# lvc.net
KiCad netlist of a schematic drawn in EAGLE
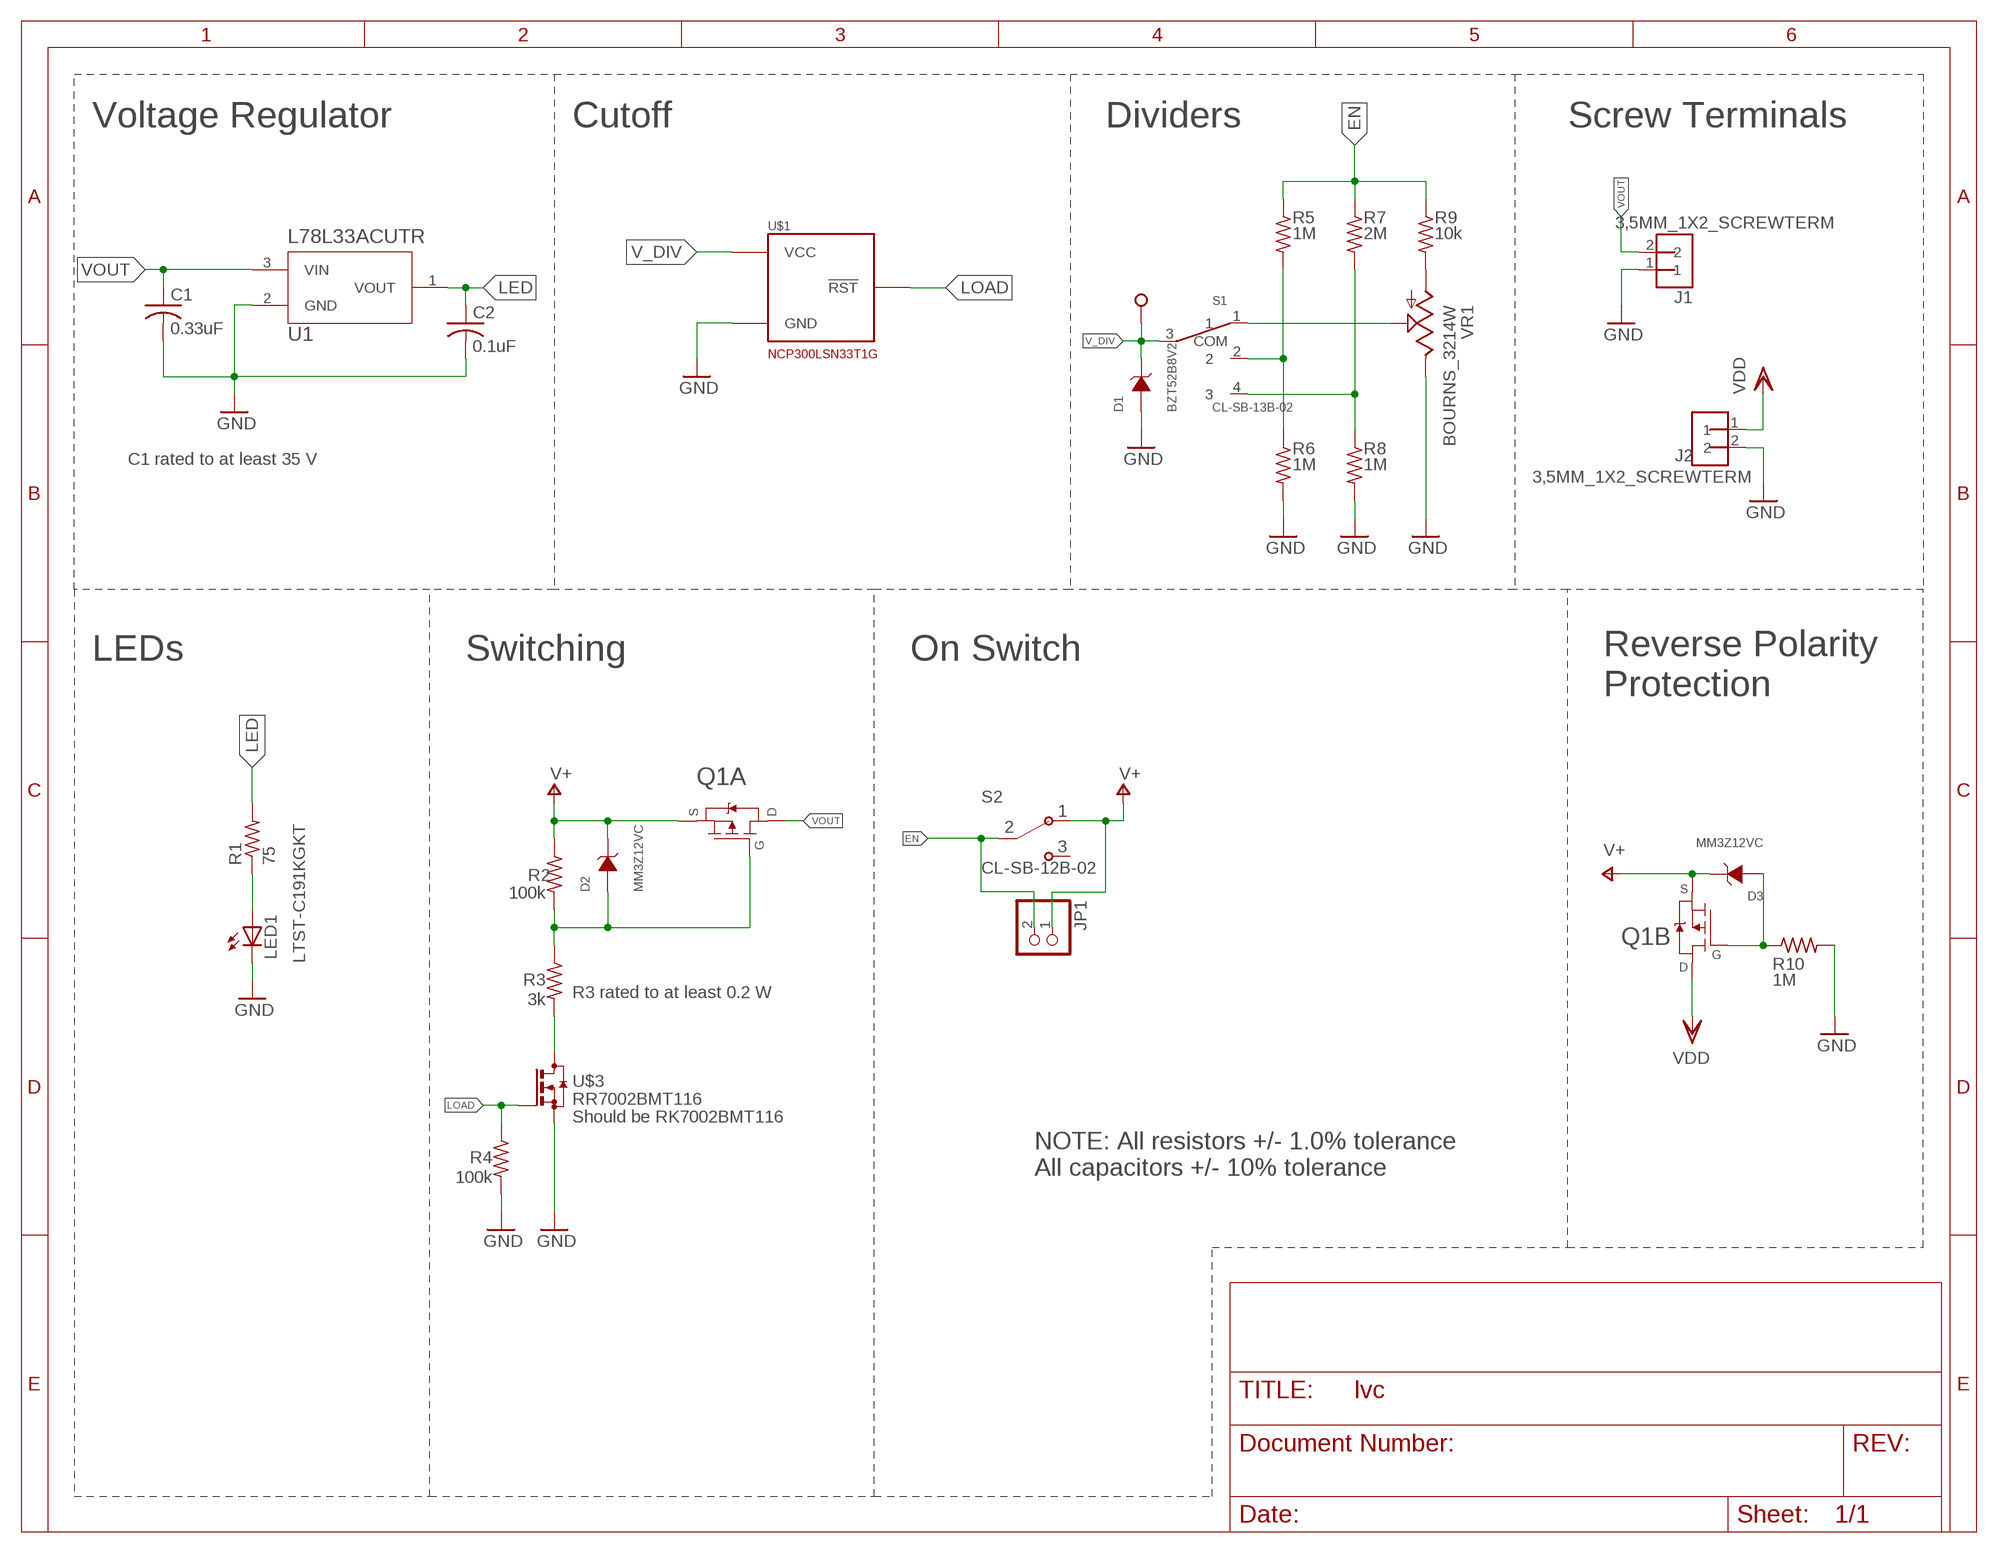
[diagram p0: schematic, sheet 1]

(export (version "E")
  (design (tool "Eeschema 10.0.6"))
  (components
    (comp (ref "C1")
      (value "0.33uF")
      (footprint "eagle-import:C0603")
      (libsource (lib "eagle-import") (part "C-USC0603"))
    )
    (comp (ref "C2")
      (value "0.1uF")
      (footprint "eagle-import:C0603")
      (libsource (lib "eagle-import") (part "C-USC0603"))
    )
    (comp (ref "D1")
      (value "BZT52B8V2")
      (footprint "eagle-import:SOD123")
      (libsource (lib "eagle-import") (part "BZT52B8V2"))
    )
    (comp (ref "D2")
      (value "MM3Z12VC")
      (footprint "eagle-import:SOD-323F")
      (libsource (lib "eagle-import") (part "MM3Z12VC"))
    )
    (comp (ref "D3")
      (value "MM3Z12VC")
      (footprint "eagle-import:SOD-323F")
      (libsource (lib "eagle-import") (part "MM3Z12VC"))
    )
    (comp (ref "J1")
      (value "3,5MM_1X2_SCREWTERM")
      (footprint "eagle-import:3.5MM_1X2")
      (libsource (lib "eagle-import") (part "3,5MM_1X2_SCREWTERM"))
    )
    (comp (ref "J2")
      (value "3,5MM_1X2_SCREWTERM")
      (footprint "eagle-import:3.5MM_1X2")
      (libsource (lib "eagle-import") (part "3,5MM_1X2_SCREWTERM"))
    )
    (comp (ref "JP1")
      (value "PINHD-1X2")
      (footprint "eagle-import:1X02")
      (libsource (lib "eagle-import") (part "PINHD-1X2"))
    )
    (comp (ref "LED1")
      (value "LEDCHIPLED_0603")
      (footprint "eagle-import:CHIPLED_0603")
      (libsource (lib "eagle-import") (part "LEDCHIPLED_0603"))
    )
    (comp (ref "Q1")
      (value "SI7997DP")
      (footprint "eagle-import:POWERPAK-SO-8-DUAL")
      (libsource (lib "eagle-import") (part "SI7997DP"))
    )
    (comp (ref "R1")
      (value "75")
      (footprint "eagle-import:R0603")
      (libsource (lib "eagle-import") (part "R-US_R0603"))
    )
    (comp (ref "R2")
      (value "100k")
      (footprint "eagle-import:R0603")
      (libsource (lib "eagle-import") (part "resistor_348_R-US_R0603"))
    )
    (comp (ref "R3")
      (value "3k")
      (footprint "eagle-import:R0603")
      (libsource (lib "eagle-import") (part "resistor_348_R-US_R0603"))
    )
    (comp (ref "R4")
      (value "100k")
      (footprint "eagle-import:R0603")
      (libsource (lib "eagle-import") (part "resistor_348_R-US_R0603"))
    )
    (comp (ref "R5")
      (value "1M")
      (footprint "eagle-import:R0603")
      (libsource (lib "eagle-import") (part "resistor_348_R-US_R0603"))
    )
    (comp (ref "R6")
      (value "1M")
      (footprint "eagle-import:R0603")
      (libsource (lib "eagle-import") (part "resistor_348_R-US_R0603"))
    )
    (comp (ref "R7")
      (value "2M")
      (footprint "eagle-import:R0603")
      (libsource (lib "eagle-import") (part "resistor_348_R-US_R0603"))
    )
    (comp (ref "R8")
      (value "1M")
      (footprint "eagle-import:R0603")
      (libsource (lib "eagle-import") (part "resistor_348_R-US_R0603"))
    )
    (comp (ref "R9")
      (value "10k")
      (footprint "eagle-import:R0603")
      (libsource (lib "eagle-import") (part "resistor_348_R-US_R0603"))
    )
    (comp (ref "R10")
      (value "1M")
      (footprint "eagle-import:R0603")
      (libsource (lib "eagle-import") (part "resistor_348_R-US_R0603"))
    )
    (comp (ref "S1")
      (value "CL-SB-13B-02")
      (footprint "eagle-import:CL-SB-13B")
      (libsource (lib "eagle-import") (part "CL-SB-13B-02"))
    )
    (comp (ref "S2")
      (value "CL-SB-12B-02")
      (footprint "eagle-import:CL-SB-12B")
      (libsource (lib "eagle-import") (part "CL-SB-12B-02"))
    )
    (comp (ref "TP1")
      (value "TESTPOINT")
      (footprint "eagle-import:TP_2.5MM")
      (libsource (lib "eagle-import") (part "TESTPOINT"))
    )
    (comp (ref "U$1")
      (value "NCP300LSN33T1G")
      (footprint "eagle-import:SOT23-5")
      (libsource (lib "eagle-import") (part "NCP300LSN33T1G"))
    )
    (comp (ref "U$3")
      (value "RR7002BMT116")
      (footprint "eagle-import:SOT23")
      (libsource (lib "eagle-import") (part "RR7002BMT116"))
    )
    (comp (ref "U1")
      (value "L78L33ACUTR")
      (footprint "eagle-import:SOT-89")
      (libsource (lib "eagle-import") (part "L78L33ACUTR"))
    )
    (comp (ref "VR1")
      (value "BOURNS_3214W")
      (footprint "eagle-import:J-LEAD_TOP_ADJ")
      (libsource (lib "eagle-import") (part "BOURNS_3214W"))
    )
  )
  (nets
    (net (code "1") (name "EN") (class "Default")
      (node (ref "JP1") (pin "2") (pinfunction "2_2") (pintype "passive"))
      (node (ref "R5") (pin "1") (pinfunction "1_1") (pintype "passive"))
      (node (ref "R7") (pin "1") (pinfunction "1_1") (pintype "passive"))
      (node (ref "R9") (pin "1") (pinfunction "1_1") (pintype "passive"))
      (node (ref "S2") (pin "1") (pinfunction "P$1_1") (pintype "bidirectional"))
    )
    (net (code "2") (name "GND") (class "Default")
      (node (ref "C1") (pin "2") (pinfunction "2_2") (pintype "passive"))
      (node (ref "C2") (pin "2") (pinfunction "2_2") (pintype "passive"))
      (node (ref "D1") (pin "A") (pinfunction "A_A") (pintype "bidirectional"))
      (node (ref "J1") (pin "1") (pinfunction "1_1") (pintype "bidirectional"))
      (node (ref "J2") (pin "2") (pinfunction "2_2") (pintype "bidirectional"))
      (node (ref "LED1") (pin "C") (pinfunction "C_C") (pintype "passive"))
      (node (ref "R10") (pin "2") (pinfunction "2_2") (pintype "passive"))
      (node (ref "R4") (pin "2") (pinfunction "2_2") (pintype "passive"))
      (node (ref "R6") (pin "2") (pinfunction "2_2") (pintype "passive"))
      (node (ref "R8") (pin "2") (pinfunction "2_2") (pintype "passive"))
      (node (ref "U$1") (pin "3") (pinfunction "GND_3") (pintype "power_in"))
      (node (ref "U$3") (pin "2") (pinfunction "S_2") (pintype "passive"))
      (node (ref "U1") (pin "2") (pinfunction "GND_2") (pintype "passive"))
      (node (ref "VR1") (pin "3") (pinfunction "E_3") (pintype "passive"))
    )
    (net (code "3") (name "LED") (class "Default")
      (node (ref "C2") (pin "1") (pinfunction "1_1") (pintype "passive"))
      (node (ref "R1") (pin "2") (pinfunction "2_2") (pintype "passive"))
      (node (ref "U1") (pin "1") (pinfunction "VOUT_1") (pintype "output"))
    )
    (net (code "4") (name "LOAD") (class "Default")
      (node (ref "R4") (pin "1") (pinfunction "1_1") (pintype "passive"))
      (node (ref "U$1") (pin "1") (pinfunction "~{RST}_1") (pintype "bidirectional"))
      (node (ref "U$3") (pin "1") (pinfunction "G_1") (pintype "passive"))
    )
    (net (code "5") (name "Net-(D2-A)") (class "Default")
      (node (ref "D2") (pin "1") (pinfunction "A_1") (pintype "bidirectional"))
      (node (ref "Q1") (pin "4") (pinfunction "G_4") (pintype "bidirectional"))
      (node (ref "R2") (pin "2") (pinfunction "2_2") (pintype "passive"))
      (node (ref "R3") (pin "1") (pinfunction "1_1") (pintype "passive"))
    )
    (net (code "6") (name "Net-(D3-A)") (class "Default")
      (node (ref "D3") (pin "1") (pinfunction "A_1") (pintype "bidirectional"))
      (node (ref "Q1") (pin "2") (pinfunction "G_2") (pintype "bidirectional"))
      (node (ref "R10") (pin "1") (pinfunction "1_1") (pintype "passive"))
    )
    (net (code "7") (name "Net-(LED1-PadA)") (class "Default")
      (node (ref "LED1") (pin "A") (pinfunction "A_A") (pintype "passive"))
      (node (ref "R1") (pin "1") (pinfunction "1_1") (pintype "passive"))
    )
    (net (code "8") (name "Net-(R5-Pad2)") (class "Default")
      (node (ref "R5") (pin "2") (pinfunction "2_2") (pintype "passive"))
      (node (ref "R6") (pin "1") (pinfunction "1_1") (pintype "passive"))
      (node (ref "S1") (pin "2") (pinfunction "2_2") (pintype "bidirectional"))
    )
    (net (code "9") (name "Net-(S1-3)") (class "Default")
      (node (ref "R7") (pin "2") (pinfunction "2_2") (pintype "passive"))
      (node (ref "R8") (pin "1") (pinfunction "1_1") (pintype "passive"))
      (node (ref "S1") (pin "4") (pinfunction "3_4") (pintype "bidirectional"))
    )
    (net (code "10") (name "Net-(U$3-D)") (class "Default")
      (node (ref "R3") (pin "2") (pinfunction "2_2") (pintype "passive"))
      (node (ref "U$3") (pin "3") (pinfunction "D_3") (pintype "passive"))
    )
    (net (code "11") (name "Net-(VR1-A)") (class "Default")
      (node (ref "R9") (pin "2") (pinfunction "2_2") (pintype "passive"))
      (node (ref "VR1") (pin "1") (pinfunction "A_1") (pintype "passive"))
    )
    (net (code "12") (name "Net-(VR1-S)") (class "Default")
      (node (ref "S1") (pin "1") (pinfunction "1_1") (pintype "bidirectional"))
      (node (ref "VR1") (pin "2") (pinfunction "S_2") (pintype "passive"))
    )
    (net (code "13") (name "V+") (class "Default")
      (node (ref "D2") (pin "2") (pinfunction "C_2") (pintype "bidirectional"))
      (node (ref "D3") (pin "2") (pinfunction "C_2") (pintype "bidirectional"))
      (node (ref "JP1") (pin "1") (pinfunction "1_1") (pintype "passive"))
      (node (ref "Q1") (pin "1") (pinfunction "S_1") (pintype "bidirectional"))
      (node (ref "Q1") (pin "3") (pinfunction "S_3") (pintype "bidirectional"))
      (node (ref "R2") (pin "1") (pinfunction "1_1") (pintype "passive"))
      (node (ref "S2") (pin "2") (pinfunction "P$2_2") (pintype "bidirectional"))
    )
    (net (code "14") (name "VDD") (class "Default")
      (node (ref "J2") (pin "1") (pinfunction "1_1") (pintype "bidirectional"))
      (node (ref "Q1") (pin "7") (pinfunction "D_7") (pintype "bidirectional"))
      (node (ref "Q1") (pin "8") (pinfunction "D_8") (pintype "bidirectional"))
      (node (ref "Q1") (pin "8L") (pinfunction "D_8L") (pintype "bidirectional"))
    )
    (net (code "15") (name "VOUT") (class "Default")
      (node (ref "C1") (pin "1") (pinfunction "1_1") (pintype "passive"))
      (node (ref "J1") (pin "2") (pinfunction "2_2") (pintype "bidirectional"))
      (node (ref "Q1") (pin "5") (pinfunction "D_5") (pintype "bidirectional"))
      (node (ref "Q1") (pin "5L") (pinfunction "D_5L") (pintype "bidirectional"))
      (node (ref "Q1") (pin "6") (pinfunction "D_6") (pintype "bidirectional"))
      (node (ref "U1") (pin "3") (pinfunction "VIN_3") (pintype "input"))
    )
    (net (code "16") (name "V_DIV") (class "Default")
      (node (ref "D1") (pin "C") (pinfunction "C_C") (pintype "bidirectional"))
      (node (ref "S1") (pin "3") (pinfunction "COM_3") (pintype "bidirectional"))
      (node (ref "TP1") (pin "P$1") (pinfunction "P$1_P$1") (pintype "bidirectional"))
      (node (ref "U$1") (pin "2") (pinfunction "VCC_2") (pintype "power_in"))
    )
    (net (code "17") (name "unconnected-(S2-P$3-Pad3)") (class "Default")
      (node (ref "S2") (pin "3") (pinfunction "P$3_3") (pintype "bidirectional"))
    )
  )
)
